# right.net
KiCad netlist of a schematic drawn in EAGLE
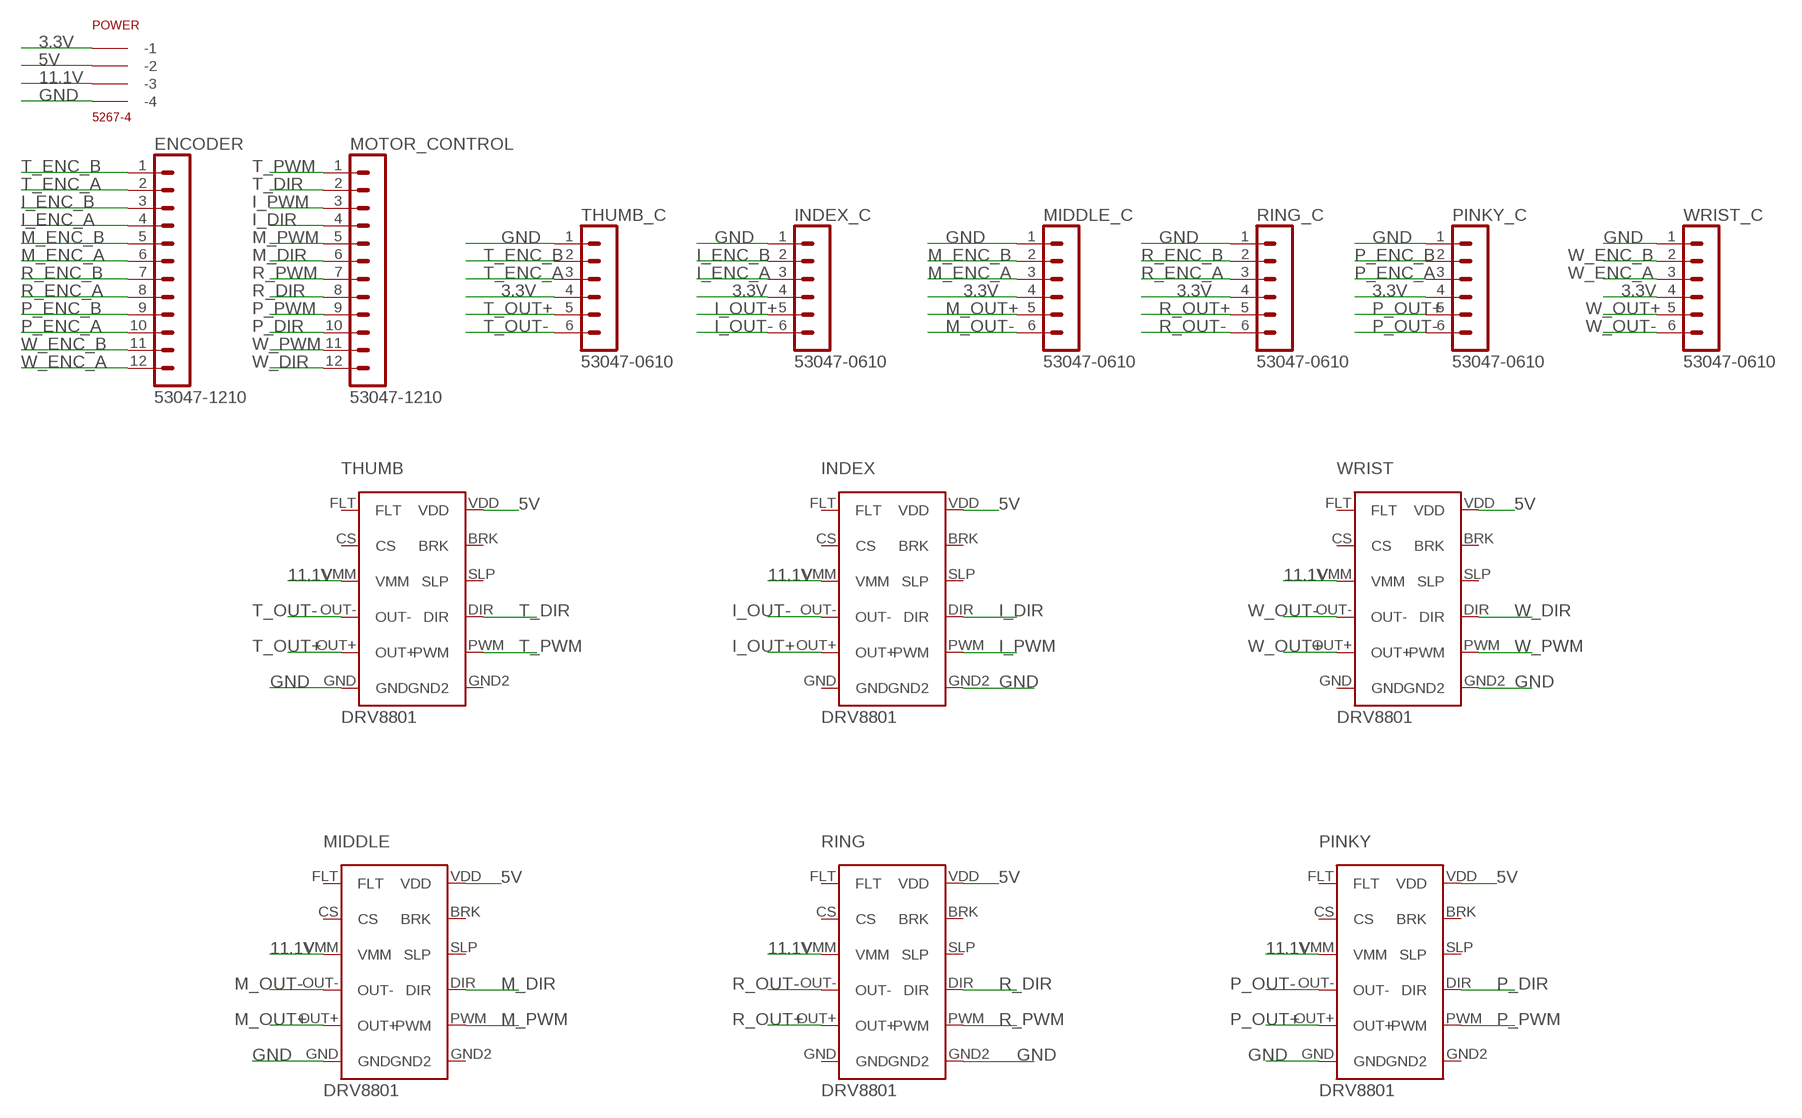
[diagram p0: schematic, sheet 1]

(export (version "E")
  (design (tool "Eeschema 10.0.6"))
  (components
    (comp (ref "ENCODER")
      (value "53047-1210")
      (footprint "eagle-import:53047-1210")
      (libsource (lib "eagle-import") (part "53047-1210"))
    )
    (comp (ref "INDEX")
      (value "DRV8801")
      (footprint "eagle-import:DRV8801")
      (libsource (lib "eagle-import") (part "DRV8801"))
    )
    (comp (ref "INDEX_C")
      (value "53047-0610")
      (footprint "eagle-import:53047-0610")
      (libsource (lib "eagle-import") (part "53047-0610"))
    )
    (comp (ref "MIDDLE")
      (value "DRV8801")
      (footprint "eagle-import:DRV8801")
      (libsource (lib "eagle-import") (part "DRV8801"))
    )
    (comp (ref "MIDDLE_C")
      (value "53047-0610")
      (footprint "eagle-import:53047-0610")
      (libsource (lib "eagle-import") (part "53047-0610"))
    )
    (comp (ref "MOTOR_CONTROL")
      (value "53047-1210")
      (footprint "eagle-import:53047-1210")
      (libsource (lib "eagle-import") (part "53047-1210"))
    )
    (comp (ref "PINKY")
      (value "DRV8801")
      (footprint "eagle-import:DRV8801")
      (libsource (lib "eagle-import") (part "DRV8801"))
    )
    (comp (ref "PINKY_C")
      (value "53047-0610")
      (footprint "eagle-import:53047-0610")
      (libsource (lib "eagle-import") (part "53047-0610"))
    )
    (comp (ref "POWER")
      (value "5267-4")
      (footprint "eagle-import:5267-4")
      (libsource (lib "eagle-import") (part "5267-4"))
    )
    (comp (ref "RING")
      (value "DRV8801")
      (footprint "eagle-import:DRV8801")
      (libsource (lib "eagle-import") (part "DRV8801"))
    )
    (comp (ref "RING_C")
      (value "53047-0610")
      (footprint "eagle-import:53047-0610")
      (libsource (lib "eagle-import") (part "53047-0610"))
    )
    (comp (ref "THUMB")
      (value "DRV8801")
      (footprint "eagle-import:DRV8801")
      (libsource (lib "eagle-import") (part "DRV8801"))
    )
    (comp (ref "THUMB_C")
      (value "53047-0610")
      (footprint "eagle-import:53047-0610")
      (libsource (lib "eagle-import") (part "53047-0610"))
    )
    (comp (ref "WRIST")
      (value "DRV8801")
      (footprint "eagle-import:DRV8801")
      (libsource (lib "eagle-import") (part "DRV8801"))
    )
    (comp (ref "WRIST_C")
      (value "53047-0610")
      (footprint "eagle-import:53047-0610")
      (libsource (lib "eagle-import") (part "53047-0610"))
    )
  )
  (nets
    (net (code "1") (name "/3.3V") (class "Default")
      (node (ref "INDEX_C") (pin "4") (pinfunction "4_4") (pintype "passive"))
      (node (ref "MIDDLE_C") (pin "4") (pinfunction "4_4") (pintype "passive"))
      (node (ref "PINKY_C") (pin "4") (pinfunction "4_4") (pintype "passive"))
      (node (ref "POWER") (pin "P$1") (pinfunction "-1_P$1") (pintype "bidirectional"))
      (node (ref "RING_C") (pin "4") (pinfunction "4_4") (pintype "passive"))
      (node (ref "THUMB_C") (pin "4") (pinfunction "4_4") (pintype "passive"))
      (node (ref "WRIST_C") (pin "4") (pinfunction "4_4") (pintype "passive"))
    )
    (net (code "2") (name "/5V") (class "Default")
      (node (ref "INDEX") (pin "VDD") (pinfunction "VDD_VDD") (pintype "bidirectional"))
      (node (ref "MIDDLE") (pin "VDD") (pinfunction "VDD_VDD") (pintype "bidirectional"))
      (node (ref "PINKY") (pin "VDD") (pinfunction "VDD_VDD") (pintype "bidirectional"))
      (node (ref "POWER") (pin "P$2") (pinfunction "-2_P$2") (pintype "bidirectional"))
      (node (ref "RING") (pin "VDD") (pinfunction "VDD_VDD") (pintype "bidirectional"))
      (node (ref "THUMB") (pin "VDD") (pinfunction "VDD_VDD") (pintype "bidirectional"))
      (node (ref "WRIST") (pin "VDD") (pinfunction "VDD_VDD") (pintype "bidirectional"))
    )
    (net (code "3") (name "/11.1V") (class "Default")
      (node (ref "INDEX") (pin "VMM") (pinfunction "VMM_VMM") (pintype "bidirectional"))
      (node (ref "MIDDLE") (pin "VMM") (pinfunction "VMM_VMM") (pintype "bidirectional"))
      (node (ref "PINKY") (pin "VMM") (pinfunction "VMM_VMM") (pintype "bidirectional"))
      (node (ref "POWER") (pin "P$3") (pinfunction "-3_P$3") (pintype "bidirectional"))
      (node (ref "RING") (pin "VMM") (pinfunction "VMM_VMM") (pintype "bidirectional"))
      (node (ref "THUMB") (pin "VMM") (pinfunction "VMM_VMM") (pintype "bidirectional"))
      (node (ref "WRIST") (pin "VMM") (pinfunction "VMM_VMM") (pintype "bidirectional"))
    )
    (net (code "4") (name "/GND") (class "Default")
      (node (ref "INDEX") (pin "GND2") (pinfunction "GND2_GND2") (pintype "bidirectional"))
      (node (ref "INDEX_C") (pin "1") (pinfunction "1_1") (pintype "passive"))
      (node (ref "MIDDLE") (pin "GND") (pinfunction "GND_GND") (pintype "bidirectional"))
      (node (ref "MIDDLE_C") (pin "1") (pinfunction "1_1") (pintype "passive"))
      (node (ref "PINKY") (pin "GND") (pinfunction "GND_GND") (pintype "bidirectional"))
      (node (ref "PINKY_C") (pin "1") (pinfunction "1_1") (pintype "passive"))
      (node (ref "POWER") (pin "P$4") (pinfunction "-4_P$4") (pintype "bidirectional"))
      (node (ref "RING") (pin "GND2") (pinfunction "GND2_GND2") (pintype "bidirectional"))
      (node (ref "RING_C") (pin "1") (pinfunction "1_1") (pintype "passive"))
      (node (ref "THUMB") (pin "GND") (pinfunction "GND_GND") (pintype "bidirectional"))
      (node (ref "THUMB_C") (pin "1") (pinfunction "1_1") (pintype "passive"))
      (node (ref "WRIST") (pin "GND2") (pinfunction "GND2_GND2") (pintype "bidirectional"))
      (node (ref "WRIST_C") (pin "1") (pinfunction "1_1") (pintype "passive"))
    )
    (net (code "5") (name "/I_DIR") (class "Default")
      (node (ref "INDEX") (pin "DIR") (pinfunction "DIR_DIR") (pintype "bidirectional"))
      (node (ref "MOTOR_CONTROL") (pin "4") (pinfunction "4_4") (pintype "passive"))
    )
    (net (code "6") (name "/I_ENC_A") (class "Default")
      (node (ref "ENCODER") (pin "4") (pinfunction "4_4") (pintype "passive"))
      (node (ref "INDEX_C") (pin "3") (pinfunction "3_3") (pintype "passive"))
    )
    (net (code "7") (name "/I_ENC_B") (class "Default")
      (node (ref "ENCODER") (pin "3") (pinfunction "3_3") (pintype "passive"))
      (node (ref "INDEX_C") (pin "2") (pinfunction "2_2") (pintype "passive"))
    )
    (net (code "8") (name "/I_OUT+") (class "Default")
      (node (ref "INDEX") (pin "OUT+") (pinfunction "OUT+_OUT+") (pintype "bidirectional"))
      (node (ref "INDEX_C") (pin "5") (pinfunction "5_5") (pintype "passive"))
    )
    (net (code "9") (name "/I_OUT-") (class "Default")
      (node (ref "INDEX") (pin "OUT-") (pinfunction "OUT-_OUT-") (pintype "bidirectional"))
      (node (ref "INDEX_C") (pin "6") (pinfunction "6_6") (pintype "passive"))
    )
    (net (code "10") (name "/I_PWM") (class "Default")
      (node (ref "INDEX") (pin "PWM") (pinfunction "PWM_PWM") (pintype "bidirectional"))
      (node (ref "MOTOR_CONTROL") (pin "3") (pinfunction "3_3") (pintype "passive"))
    )
    (net (code "11") (name "/M_DIR") (class "Default")
      (node (ref "MIDDLE") (pin "DIR") (pinfunction "DIR_DIR") (pintype "bidirectional"))
      (node (ref "MOTOR_CONTROL") (pin "6") (pinfunction "6_6") (pintype "passive"))
    )
    (net (code "12") (name "/M_ENC_A") (class "Default")
      (node (ref "ENCODER") (pin "6") (pinfunction "6_6") (pintype "passive"))
      (node (ref "MIDDLE_C") (pin "3") (pinfunction "3_3") (pintype "passive"))
    )
    (net (code "13") (name "/M_ENC_B") (class "Default")
      (node (ref "ENCODER") (pin "5") (pinfunction "5_5") (pintype "passive"))
      (node (ref "MIDDLE_C") (pin "2") (pinfunction "2_2") (pintype "passive"))
    )
    (net (code "14") (name "/M_OUT+") (class "Default")
      (node (ref "MIDDLE") (pin "OUT+") (pinfunction "OUT+_OUT+") (pintype "bidirectional"))
      (node (ref "MIDDLE_C") (pin "5") (pinfunction "5_5") (pintype "passive"))
    )
    (net (code "15") (name "/M_OUT-") (class "Default")
      (node (ref "MIDDLE") (pin "OUT-") (pinfunction "OUT-_OUT-") (pintype "bidirectional"))
      (node (ref "MIDDLE_C") (pin "6") (pinfunction "6_6") (pintype "passive"))
    )
    (net (code "16") (name "/M_PWM") (class "Default")
      (node (ref "MIDDLE") (pin "PWM") (pinfunction "PWM_PWM") (pintype "bidirectional"))
      (node (ref "MOTOR_CONTROL") (pin "5") (pinfunction "5_5") (pintype "passive"))
    )
    (net (code "17") (name "/P_DIR") (class "Default")
      (node (ref "MOTOR_CONTROL") (pin "10") (pinfunction "10_10") (pintype "passive"))
      (node (ref "PINKY") (pin "DIR") (pinfunction "DIR_DIR") (pintype "bidirectional"))
    )
    (net (code "18") (name "/P_ENC_A") (class "Default")
      (node (ref "ENCODER") (pin "10") (pinfunction "10_10") (pintype "passive"))
      (node (ref "PINKY_C") (pin "3") (pinfunction "3_3") (pintype "passive"))
    )
    (net (code "19") (name "/P_ENC_B") (class "Default")
      (node (ref "ENCODER") (pin "9") (pinfunction "9_9") (pintype "passive"))
      (node (ref "PINKY_C") (pin "2") (pinfunction "2_2") (pintype "passive"))
    )
    (net (code "20") (name "/P_OUT+") (class "Default")
      (node (ref "PINKY") (pin "OUT+") (pinfunction "OUT+_OUT+") (pintype "bidirectional"))
      (node (ref "PINKY_C") (pin "5") (pinfunction "5_5") (pintype "passive"))
    )
    (net (code "21") (name "/P_OUT-") (class "Default")
      (node (ref "PINKY") (pin "OUT-") (pinfunction "OUT-_OUT-") (pintype "bidirectional"))
      (node (ref "PINKY_C") (pin "6") (pinfunction "6_6") (pintype "passive"))
    )
    (net (code "22") (name "/P_PWM") (class "Default")
      (node (ref "MOTOR_CONTROL") (pin "9") (pinfunction "9_9") (pintype "passive"))
      (node (ref "PINKY") (pin "PWM") (pinfunction "PWM_PWM") (pintype "bidirectional"))
    )
    (net (code "23") (name "/R_DIR") (class "Default")
      (node (ref "MOTOR_CONTROL") (pin "8") (pinfunction "8_8") (pintype "passive"))
      (node (ref "RING") (pin "DIR") (pinfunction "DIR_DIR") (pintype "bidirectional"))
    )
    (net (code "24") (name "/R_ENC_A") (class "Default")
      (node (ref "ENCODER") (pin "8") (pinfunction "8_8") (pintype "passive"))
      (node (ref "RING_C") (pin "3") (pinfunction "3_3") (pintype "passive"))
    )
    (net (code "25") (name "/R_ENC_B") (class "Default")
      (node (ref "ENCODER") (pin "7") (pinfunction "7_7") (pintype "passive"))
      (node (ref "RING_C") (pin "2") (pinfunction "2_2") (pintype "passive"))
    )
    (net (code "26") (name "/R_OUT+") (class "Default")
      (node (ref "RING") (pin "OUT+") (pinfunction "OUT+_OUT+") (pintype "bidirectional"))
      (node (ref "RING_C") (pin "5") (pinfunction "5_5") (pintype "passive"))
    )
    (net (code "27") (name "/R_OUT-") (class "Default")
      (node (ref "RING") (pin "OUT-") (pinfunction "OUT-_OUT-") (pintype "bidirectional"))
      (node (ref "RING_C") (pin "6") (pinfunction "6_6") (pintype "passive"))
    )
    (net (code "28") (name "/R_PWM") (class "Default")
      (node (ref "MOTOR_CONTROL") (pin "7") (pinfunction "7_7") (pintype "passive"))
      (node (ref "RING") (pin "PWM") (pinfunction "PWM_PWM") (pintype "bidirectional"))
    )
    (net (code "29") (name "/T_DIR") (class "Default")
      (node (ref "MOTOR_CONTROL") (pin "2") (pinfunction "2_2") (pintype "passive"))
      (node (ref "THUMB") (pin "DIR") (pinfunction "DIR_DIR") (pintype "bidirectional"))
    )
    (net (code "30") (name "/T_ENC_A") (class "Default")
      (node (ref "ENCODER") (pin "2") (pinfunction "2_2") (pintype "passive"))
      (node (ref "THUMB_C") (pin "3") (pinfunction "3_3") (pintype "passive"))
    )
    (net (code "31") (name "/T_ENC_B") (class "Default")
      (node (ref "ENCODER") (pin "1") (pinfunction "1_1") (pintype "passive"))
      (node (ref "THUMB_C") (pin "2") (pinfunction "2_2") (pintype "passive"))
    )
    (net (code "32") (name "/T_OUT+") (class "Default")
      (node (ref "THUMB") (pin "OUT+") (pinfunction "OUT+_OUT+") (pintype "bidirectional"))
      (node (ref "THUMB_C") (pin "5") (pinfunction "5_5") (pintype "passive"))
    )
    (net (code "33") (name "/T_OUT-") (class "Default")
      (node (ref "THUMB") (pin "OUT-") (pinfunction "OUT-_OUT-") (pintype "bidirectional"))
      (node (ref "THUMB_C") (pin "6") (pinfunction "6_6") (pintype "passive"))
    )
    (net (code "34") (name "/T_PWM") (class "Default")
      (node (ref "MOTOR_CONTROL") (pin "1") (pinfunction "1_1") (pintype "passive"))
      (node (ref "THUMB") (pin "PWM") (pinfunction "PWM_PWM") (pintype "bidirectional"))
    )
    (net (code "35") (name "/W_DIR") (class "Default")
      (node (ref "MOTOR_CONTROL") (pin "12") (pinfunction "12_12") (pintype "passive"))
      (node (ref "WRIST") (pin "DIR") (pinfunction "DIR_DIR") (pintype "bidirectional"))
    )
    (net (code "36") (name "/W_ENC_A") (class "Default")
      (node (ref "ENCODER") (pin "12") (pinfunction "12_12") (pintype "passive"))
      (node (ref "WRIST_C") (pin "3") (pinfunction "3_3") (pintype "passive"))
    )
    (net (code "37") (name "/W_ENC_B") (class "Default")
      (node (ref "ENCODER") (pin "11") (pinfunction "11_11") (pintype "passive"))
      (node (ref "WRIST_C") (pin "2") (pinfunction "2_2") (pintype "passive"))
    )
    (net (code "38") (name "/W_OUT+") (class "Default")
      (node (ref "WRIST") (pin "OUT+") (pinfunction "OUT+_OUT+") (pintype "bidirectional"))
      (node (ref "WRIST_C") (pin "5") (pinfunction "5_5") (pintype "passive"))
    )
    (net (code "39") (name "/W_OUT-") (class "Default")
      (node (ref "WRIST") (pin "OUT-") (pinfunction "OUT-_OUT-") (pintype "bidirectional"))
      (node (ref "WRIST_C") (pin "6") (pinfunction "6_6") (pintype "passive"))
    )
    (net (code "40") (name "/W_PWM") (class "Default")
      (node (ref "MOTOR_CONTROL") (pin "11") (pinfunction "11_11") (pintype "passive"))
      (node (ref "WRIST") (pin "PWM") (pinfunction "PWM_PWM") (pintype "bidirectional"))
    )
    (net (code "41") (name "unconnected-(INDEX-PadBRK)") (class "Default")
      (node (ref "INDEX") (pin "BRK") (pinfunction "BRK_BRK") (pintype "bidirectional"))
    )
    (net (code "42") (name "unconnected-(INDEX-PadCS)") (class "Default")
      (node (ref "INDEX") (pin "CS") (pinfunction "CS_CS") (pintype "bidirectional"))
    )
    (net (code "43") (name "unconnected-(INDEX-PadFLT)") (class "Default")
      (node (ref "INDEX") (pin "FLT") (pinfunction "FLT_FLT") (pintype "bidirectional"))
    )
    (net (code "44") (name "unconnected-(INDEX-PadGND)") (class "Default")
      (node (ref "INDEX") (pin "GND") (pinfunction "GND_GND") (pintype "bidirectional"))
    )
    (net (code "45") (name "unconnected-(INDEX-PadSLP)") (class "Default")
      (node (ref "INDEX") (pin "SLP") (pinfunction "SLP_SLP") (pintype "bidirectional"))
    )
    (net (code "46") (name "unconnected-(MIDDLE-PadBRK)") (class "Default")
      (node (ref "MIDDLE") (pin "BRK") (pinfunction "BRK_BRK") (pintype "bidirectional"))
    )
    (net (code "47") (name "unconnected-(MIDDLE-PadCS)") (class "Default")
      (node (ref "MIDDLE") (pin "CS") (pinfunction "CS_CS") (pintype "bidirectional"))
    )
    (net (code "48") (name "unconnected-(MIDDLE-PadFLT)") (class "Default")
      (node (ref "MIDDLE") (pin "FLT") (pinfunction "FLT_FLT") (pintype "bidirectional"))
    )
    (net (code "49") (name "unconnected-(MIDDLE-PadGND2)") (class "Default")
      (node (ref "MIDDLE") (pin "GND2") (pinfunction "GND2_GND2") (pintype "bidirectional"))
    )
    (net (code "50") (name "unconnected-(MIDDLE-PadSLP)") (class "Default")
      (node (ref "MIDDLE") (pin "SLP") (pinfunction "SLP_SLP") (pintype "bidirectional"))
    )
    (net (code "51") (name "unconnected-(PINKY-PadBRK)") (class "Default")
      (node (ref "PINKY") (pin "BRK") (pinfunction "BRK_BRK") (pintype "bidirectional"))
    )
    (net (code "52") (name "unconnected-(PINKY-PadCS)") (class "Default")
      (node (ref "PINKY") (pin "CS") (pinfunction "CS_CS") (pintype "bidirectional"))
    )
    (net (code "53") (name "unconnected-(PINKY-PadFLT)") (class "Default")
      (node (ref "PINKY") (pin "FLT") (pinfunction "FLT_FLT") (pintype "bidirectional"))
    )
    (net (code "54") (name "unconnected-(PINKY-PadGND2)") (class "Default")
      (node (ref "PINKY") (pin "GND2") (pinfunction "GND2_GND2") (pintype "bidirectional"))
    )
    (net (code "55") (name "unconnected-(PINKY-PadSLP)") (class "Default")
      (node (ref "PINKY") (pin "SLP") (pinfunction "SLP_SLP") (pintype "bidirectional"))
    )
    (net (code "56") (name "unconnected-(RING-PadBRK)") (class "Default")
      (node (ref "RING") (pin "BRK") (pinfunction "BRK_BRK") (pintype "bidirectional"))
    )
    (net (code "57") (name "unconnected-(RING-PadCS)") (class "Default")
      (node (ref "RING") (pin "CS") (pinfunction "CS_CS") (pintype "bidirectional"))
    )
    (net (code "58") (name "unconnected-(RING-PadFLT)") (class "Default")
      (node (ref "RING") (pin "FLT") (pinfunction "FLT_FLT") (pintype "bidirectional"))
    )
    (net (code "59") (name "unconnected-(RING-PadGND)") (class "Default")
      (node (ref "RING") (pin "GND") (pinfunction "GND_GND") (pintype "bidirectional"))
    )
    (net (code "60") (name "unconnected-(RING-PadSLP)") (class "Default")
      (node (ref "RING") (pin "SLP") (pinfunction "SLP_SLP") (pintype "bidirectional"))
    )
    (net (code "61") (name "unconnected-(THUMB-PadBRK)") (class "Default")
      (node (ref "THUMB") (pin "BRK") (pinfunction "BRK_BRK") (pintype "bidirectional"))
    )
    (net (code "62") (name "unconnected-(THUMB-PadCS)") (class "Default")
      (node (ref "THUMB") (pin "CS") (pinfunction "CS_CS") (pintype "bidirectional"))
    )
    (net (code "63") (name "unconnected-(THUMB-PadFLT)") (class "Default")
      (node (ref "THUMB") (pin "FLT") (pinfunction "FLT_FLT") (pintype "bidirectional"))
    )
    (net (code "64") (name "unconnected-(THUMB-PadGND2)") (class "Default")
      (node (ref "THUMB") (pin "GND2") (pinfunction "GND2_GND2") (pintype "bidirectional"))
    )
    (net (code "65") (name "unconnected-(THUMB-PadSLP)") (class "Default")
      (node (ref "THUMB") (pin "SLP") (pinfunction "SLP_SLP") (pintype "bidirectional"))
    )
    (net (code "66") (name "unconnected-(WRIST-PadBRK)") (class "Default")
      (node (ref "WRIST") (pin "BRK") (pinfunction "BRK_BRK") (pintype "bidirectional"))
    )
    (net (code "67") (name "unconnected-(WRIST-PadCS)") (class "Default")
      (node (ref "WRIST") (pin "CS") (pinfunction "CS_CS") (pintype "bidirectional"))
    )
    (net (code "68") (name "unconnected-(WRIST-PadFLT)") (class "Default")
      (node (ref "WRIST") (pin "FLT") (pinfunction "FLT_FLT") (pintype "bidirectional"))
    )
    (net (code "69") (name "unconnected-(WRIST-PadGND)") (class "Default")
      (node (ref "WRIST") (pin "GND") (pinfunction "GND_GND") (pintype "bidirectional"))
    )
    (net (code "70") (name "unconnected-(WRIST-PadSLP)") (class "Default")
      (node (ref "WRIST") (pin "SLP") (pinfunction "SLP_SLP") (pintype "bidirectional"))
    )
  )
)
